# inverter.net
KiCad netlist of a schematic drawn in Altium Designer
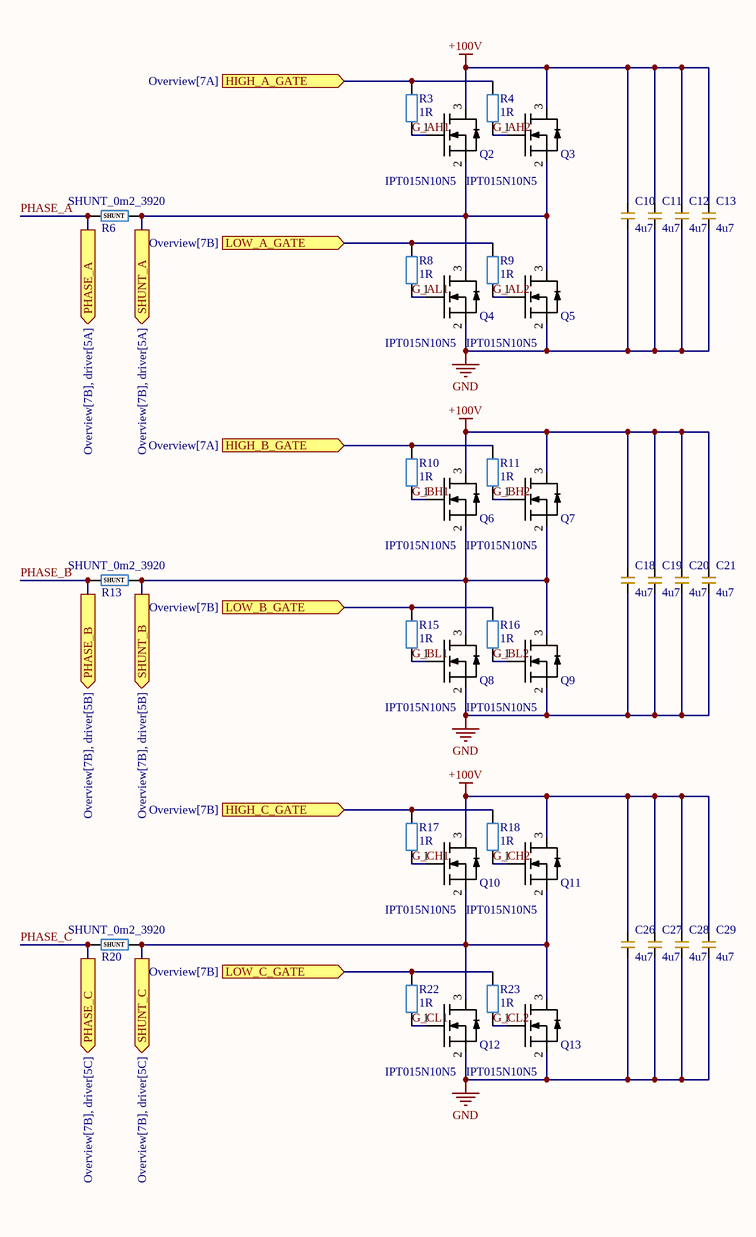
[diagram p0: inverter.SchDoc]

(export (version "E")
  (design (tool "Eeschema 10.0.6"))
  (components
    (comp (ref "C10")
      (value "4u7")
      (footprint "FS32X475K101EGG")
      (description "100V 4.7uF X7R ±10% 1210 Multilayer Ceramic Capacitors MLCC - SMD/SMT ROHS")
      (fields
        (field (name "MFR.") "PSA(Prosperity Dielectrics)")
        (field (name "MFR. PART") "FS32X475K101EGG")
      )
      (libsource (lib "Passive") (part "4u7"))
    )
    (comp (ref "C11")
      (value "4u7")
      (footprint "FS32X475K101EGG")
      (description "100V 4.7uF X7R ±10% 1210 Multilayer Ceramic Capacitors MLCC - SMD/SMT ROHS")
      (fields
        (field (name "MFR.") "PSA(Prosperity Dielectrics)")
        (field (name "MFR. PART") "FS32X475K101EGG")
      )
      (libsource (lib "Passive") (part "4u7"))
    )
    (comp (ref "C12")
      (value "4u7")
      (footprint "FS32X475K101EGG")
      (description "100V 4.7uF X7R ±10% 1210 Multilayer Ceramic Capacitors MLCC - SMD/SMT ROHS")
      (fields
        (field (name "MFR.") "PSA(Prosperity Dielectrics)")
        (field (name "MFR. PART") "FS32X475K101EGG")
      )
      (libsource (lib "Passive") (part "4u7"))
    )
    (comp (ref "C13")
      (value "4u7")
      (footprint "FS32X475K101EGG")
      (description "100V 4.7uF X7R ±10% 1210 Multilayer Ceramic Capacitors MLCC - SMD/SMT ROHS")
      (fields
        (field (name "MFR.") "PSA(Prosperity Dielectrics)")
        (field (name "MFR. PART") "FS32X475K101EGG")
      )
      (libsource (lib "Passive") (part "4u7"))
    )
    (comp (ref "C18")
      (value "4u7")
      (footprint "FS32X475K101EGG")
      (description "100V 4.7uF X7R ±10% 1210 Multilayer Ceramic Capacitors MLCC - SMD/SMT ROHS")
      (fields
        (field (name "MFR.") "PSA(Prosperity Dielectrics)")
        (field (name "MFR. PART") "FS32X475K101EGG")
      )
      (libsource (lib "Passive") (part "4u7"))
    )
    (comp (ref "C19")
      (value "4u7")
      (footprint "FS32X475K101EGG")
      (description "100V 4.7uF X7R ±10% 1210 Multilayer Ceramic Capacitors MLCC - SMD/SMT ROHS")
      (fields
        (field (name "MFR.") "PSA(Prosperity Dielectrics)")
        (field (name "MFR. PART") "FS32X475K101EGG")
      )
      (libsource (lib "Passive") (part "4u7"))
    )
    (comp (ref "C20")
      (value "4u7")
      (footprint "FS32X475K101EGG")
      (description "100V 4.7uF X7R ±10% 1210 Multilayer Ceramic Capacitors MLCC - SMD/SMT ROHS")
      (fields
        (field (name "MFR.") "PSA(Prosperity Dielectrics)")
        (field (name "MFR. PART") "FS32X475K101EGG")
      )
      (libsource (lib "Passive") (part "4u7"))
    )
    (comp (ref "C21")
      (value "4u7")
      (footprint "FS32X475K101EGG")
      (description "100V 4.7uF X7R ±10% 1210 Multilayer Ceramic Capacitors MLCC - SMD/SMT ROHS")
      (fields
        (field (name "MFR.") "PSA(Prosperity Dielectrics)")
        (field (name "MFR. PART") "FS32X475K101EGG")
      )
      (libsource (lib "Passive") (part "4u7"))
    )
    (comp (ref "C26")
      (value "4u7")
      (footprint "FS32X475K101EGG")
      (description "100V 4.7uF X7R ±10% 1210 Multilayer Ceramic Capacitors MLCC - SMD/SMT ROHS")
      (fields
        (field (name "MFR.") "PSA(Prosperity Dielectrics)")
        (field (name "MFR. PART") "FS32X475K101EGG")
      )
      (libsource (lib "Passive") (part "4u7"))
    )
    (comp (ref "C27")
      (value "4u7")
      (footprint "FS32X475K101EGG")
      (description "100V 4.7uF X7R ±10% 1210 Multilayer Ceramic Capacitors MLCC - SMD/SMT ROHS")
      (fields
        (field (name "MFR.") "PSA(Prosperity Dielectrics)")
        (field (name "MFR. PART") "FS32X475K101EGG")
      )
      (libsource (lib "Passive") (part "4u7"))
    )
    (comp (ref "C28")
      (value "4u7")
      (footprint "FS32X475K101EGG")
      (description "100V 4.7uF X7R ±10% 1210 Multilayer Ceramic Capacitors MLCC - SMD/SMT ROHS")
      (fields
        (field (name "MFR.") "PSA(Prosperity Dielectrics)")
        (field (name "MFR. PART") "FS32X475K101EGG")
      )
      (libsource (lib "Passive") (part "4u7"))
    )
    (comp (ref "C29")
      (value "4u7")
      (footprint "FS32X475K101EGG")
      (description "100V 4.7uF X7R ±10% 1210 Multilayer Ceramic Capacitors MLCC - SMD/SMT ROHS")
      (fields
        (field (name "MFR.") "PSA(Prosperity Dielectrics)")
        (field (name "MFR. PART") "FS32X475K101EGG")
      )
      (libsource (lib "Passive") (part "4u7"))
    )
    (comp (ref "Q2")
      (value "IPT015N10N5")
      (footprint "IPT015N10N5")
      (description "100V 500A 533W 1.35mΩ 1 N-channel HSOF-8 MOSFETs ROHS")
      (fields (field (name "MFR.") "Tokmas"))
      (libsource (lib "Active") (part "IPT015N10N5"))
    )
    (comp (ref "Q3")
      (value "IPT015N10N5")
      (footprint "IPT015N10N5")
      (description "100V 500A 533W 1.35mΩ 1 N-channel HSOF-8 MOSFETs ROHS")
      (fields (field (name "MFR.") "Tokmas"))
      (libsource (lib "Active") (part "IPT015N10N5"))
    )
    (comp (ref "Q4")
      (value "IPT015N10N5")
      (footprint "IPT015N10N5")
      (description "100V 500A 533W 1.35mΩ 1 N-channel HSOF-8 MOSFETs ROHS")
      (fields (field (name "MFR.") "Tokmas"))
      (libsource (lib "Active") (part "IPT015N10N5"))
    )
    (comp (ref "Q5")
      (value "IPT015N10N5")
      (footprint "IPT015N10N5")
      (description "100V 500A 533W 1.35mΩ 1 N-channel HSOF-8 MOSFETs ROHS")
      (fields (field (name "MFR.") "Tokmas"))
      (libsource (lib "Active") (part "IPT015N10N5"))
    )
    (comp (ref "Q6")
      (value "IPT015N10N5")
      (footprint "IPT015N10N5")
      (description "100V 500A 533W 1.35mΩ 1 N-channel HSOF-8 MOSFETs ROHS")
      (fields (field (name "MFR.") "Tokmas"))
      (libsource (lib "Active") (part "IPT015N10N5"))
    )
    (comp (ref "Q7")
      (value "IPT015N10N5")
      (footprint "IPT015N10N5")
      (description "100V 500A 533W 1.35mΩ 1 N-channel HSOF-8 MOSFETs ROHS")
      (fields (field (name "MFR.") "Tokmas"))
      (libsource (lib "Active") (part "IPT015N10N5"))
    )
    (comp (ref "Q8")
      (value "IPT015N10N5")
      (footprint "IPT015N10N5")
      (description "100V 500A 533W 1.35mΩ 1 N-channel HSOF-8 MOSFETs ROHS")
      (fields (field (name "MFR.") "Tokmas"))
      (libsource (lib "Active") (part "IPT015N10N5"))
    )
    (comp (ref "Q9")
      (value "IPT015N10N5")
      (footprint "IPT015N10N5")
      (description "100V 500A 533W 1.35mΩ 1 N-channel HSOF-8 MOSFETs ROHS")
      (fields (field (name "MFR.") "Tokmas"))
      (libsource (lib "Active") (part "IPT015N10N5"))
    )
    (comp (ref "Q10")
      (value "IPT015N10N5")
      (footprint "IPT015N10N5")
      (description "100V 500A 533W 1.35mΩ 1 N-channel HSOF-8 MOSFETs ROHS")
      (fields (field (name "MFR.") "Tokmas"))
      (libsource (lib "Active") (part "IPT015N10N5"))
    )
    (comp (ref "Q11")
      (value "IPT015N10N5")
      (footprint "IPT015N10N5")
      (description "100V 500A 533W 1.35mΩ 1 N-channel HSOF-8 MOSFETs ROHS")
      (fields (field (name "MFR.") "Tokmas"))
      (libsource (lib "Active") (part "IPT015N10N5"))
    )
    (comp (ref "Q12")
      (value "IPT015N10N5")
      (footprint "IPT015N10N5")
      (description "100V 500A 533W 1.35mΩ 1 N-channel HSOF-8 MOSFETs ROHS")
      (fields (field (name "MFR.") "Tokmas"))
      (libsource (lib "Active") (part "IPT015N10N5"))
    )
    (comp (ref "Q13")
      (value "IPT015N10N5")
      (footprint "IPT015N10N5")
      (description "100V 500A 533W 1.35mΩ 1 N-channel HSOF-8 MOSFETs ROHS")
      (fields (field (name "MFR.") "Tokmas"))
      (libsource (lib "Active") (part "IPT015N10N5"))
    )
    (comp (ref "R3")
      (value "1R")
      (footprint "RES_0805")
      (description "Resistor SMD 0805 Generic")
      (libsource (lib "Passive") (part "RES_0805"))
    )
    (comp (ref "R4")
      (value "1R")
      (footprint "RES_0805")
      (description "Resistor SMD 0805 Generic")
      (libsource (lib "Passive") (part "RES_0805"))
    )
    (comp (ref "R6")
      (value "SHUNT_0m2_3920")
      (footprint "ASR-M-5-0.2F-t1")
      (description "12W 0.2mΩ Patch Splitter ±200ppm/℃ ±1% 3920 Current Sense Resistors / Shunt Resistors ROHS")
      (fields (field (name "MFR. PART") "ASR-M-5-0.2F-t1") (field (name "MFR.") "Shenzhen Yezhan Elec."))
      (libsource (lib "Passive") (part "SHUNT_0m2_3920"))
    )
    (comp (ref "R8")
      (value "1R")
      (footprint "RES_0805")
      (description "Resistor SMD 0805 Generic")
      (libsource (lib "Passive") (part "RES_0805"))
    )
    (comp (ref "R9")
      (value "1R")
      (footprint "RES_0805")
      (description "Resistor SMD 0805 Generic")
      (libsource (lib "Passive") (part "RES_0805"))
    )
    (comp (ref "R10")
      (value "1R")
      (footprint "RES_0805")
      (description "Resistor SMD 0805 Generic")
      (libsource (lib "Passive") (part "RES_0805"))
    )
    (comp (ref "R11")
      (value "1R")
      (footprint "RES_0805")
      (description "Resistor SMD 0805 Generic")
      (libsource (lib "Passive") (part "RES_0805"))
    )
    (comp (ref "R13")
      (value "SHUNT_0m2_3920")
      (footprint "ASR-M-5-0.2F-t1")
      (description "12W 0.2mΩ Patch Splitter ±200ppm/℃ ±1% 3920 Current Sense Resistors / Shunt Resistors ROHS")
      (fields (field (name "MFR. PART") "ASR-M-5-0.2F-t1") (field (name "MFR.") "Shenzhen Yezhan Elec."))
      (libsource (lib "Passive") (part "SHUNT_0m2_3920"))
    )
    (comp (ref "R15")
      (value "1R")
      (footprint "RES_0805")
      (description "Resistor SMD 0805 Generic")
      (libsource (lib "Passive") (part "RES_0805"))
    )
    (comp (ref "R16")
      (value "1R")
      (footprint "RES_0805")
      (description "Resistor SMD 0805 Generic")
      (libsource (lib "Passive") (part "RES_0805"))
    )
    (comp (ref "R17")
      (value "1R")
      (footprint "RES_0805")
      (description "Resistor SMD 0805 Generic")
      (libsource (lib "Passive") (part "RES_0805"))
    )
    (comp (ref "R18")
      (value "1R")
      (footprint "RES_0805")
      (description "Resistor SMD 0805 Generic")
      (libsource (lib "Passive") (part "RES_0805"))
    )
    (comp (ref "R20")
      (value "SHUNT_0m2_3920")
      (footprint "ASR-M-5-0.2F-t1")
      (description "12W 0.2mΩ Patch Splitter ±200ppm/℃ ±1% 3920 Current Sense Resistors / Shunt Resistors ROHS")
      (fields (field (name "MFR. PART") "ASR-M-5-0.2F-t1") (field (name "MFR.") "Shenzhen Yezhan Elec."))
      (libsource (lib "Passive") (part "SHUNT_0m2_3920"))
    )
    (comp (ref "R22")
      (value "1R")
      (footprint "RES_0805")
      (description "Resistor SMD 0805 Generic")
      (libsource (lib "Passive") (part "RES_0805"))
    )
    (comp (ref "R23")
      (value "1R")
      (footprint "RES_0805")
      (description "Resistor SMD 0805 Generic")
      (libsource (lib "Passive") (part "RES_0805"))
    )
  )
  (nets
    (net (code "1") (name "+100V") (class "Default")
      (node (ref "C10") (pin "2") (pintype "passive"))
      (node (ref "C11") (pin "2") (pintype "passive"))
      (node (ref "C12") (pin "2") (pintype "passive"))
      (node (ref "C13") (pin "2") (pintype "passive"))
      (node (ref "C18") (pin "2") (pintype "passive"))
      (node (ref "C19") (pin "2") (pintype "passive"))
      (node (ref "C20") (pin "2") (pintype "passive"))
      (node (ref "C21") (pin "2") (pintype "passive"))
      (node (ref "C26") (pin "2") (pintype "passive"))
      (node (ref "C27") (pin "2") (pintype "passive"))
      (node (ref "C28") (pin "2") (pintype "passive"))
      (node (ref "C29") (pin "2") (pintype "passive"))
      (node (ref "Q10") (pin "3") (pintype "passive"))
      (node (ref "Q11") (pin "3") (pintype "passive"))
      (node (ref "Q2") (pin "3") (pintype "passive"))
      (node (ref "Q3") (pin "3") (pintype "passive"))
      (node (ref "Q6") (pin "3") (pintype "passive"))
      (node (ref "Q7") (pin "3") (pintype "passive"))
    )
    (net (code "2") (name "/G_AH1") (class "Default")
      (node (ref "Q2") (pin "1") (pinfunction "G_1") (pintype "passive"))
      (node (ref "R3") (pin "1") (pintype "passive"))
    )
    (net (code "3") (name "/G_AH2") (class "Default")
      (node (ref "Q3") (pin "1") (pinfunction "G_1") (pintype "passive"))
      (node (ref "R4") (pin "1") (pintype "passive"))
    )
    (net (code "4") (name "/G_AL1") (class "Default")
      (node (ref "Q4") (pin "1") (pinfunction "G_1") (pintype "passive"))
      (node (ref "R8") (pin "1") (pintype "passive"))
    )
    (net (code "5") (name "/G_AL2") (class "Default")
      (node (ref "Q5") (pin "1") (pinfunction "G_1") (pintype "passive"))
      (node (ref "R9") (pin "1") (pintype "passive"))
    )
    (net (code "6") (name "/G_BH1") (class "Default")
      (node (ref "Q6") (pin "1") (pinfunction "G_1") (pintype "passive"))
      (node (ref "R10") (pin "1") (pintype "passive"))
    )
    (net (code "7") (name "/G_BH2") (class "Default")
      (node (ref "Q7") (pin "1") (pinfunction "G_1") (pintype "passive"))
      (node (ref "R11") (pin "1") (pintype "passive"))
    )
    (net (code "8") (name "/G_BL1") (class "Default")
      (node (ref "Q8") (pin "1") (pinfunction "G_1") (pintype "passive"))
      (node (ref "R15") (pin "1") (pintype "passive"))
    )
    (net (code "9") (name "/G_BL2") (class "Default")
      (node (ref "Q9") (pin "1") (pinfunction "G_1") (pintype "passive"))
      (node (ref "R16") (pin "1") (pintype "passive"))
    )
    (net (code "10") (name "/G_CH1") (class "Default")
      (node (ref "Q10") (pin "1") (pinfunction "G_1") (pintype "passive"))
      (node (ref "R17") (pin "1") (pintype "passive"))
    )
    (net (code "11") (name "/G_CH2") (class "Default")
      (node (ref "Q11") (pin "1") (pinfunction "G_1") (pintype "passive"))
      (node (ref "R18") (pin "1") (pintype "passive"))
    )
    (net (code "12") (name "/G_CL1") (class "Default")
      (node (ref "Q12") (pin "1") (pinfunction "G_1") (pintype "passive"))
      (node (ref "R22") (pin "1") (pintype "passive"))
    )
    (net (code "13") (name "/G_CL2") (class "Default")
      (node (ref "Q13") (pin "1") (pinfunction "G_1") (pintype "passive"))
      (node (ref "R23") (pin "1") (pintype "passive"))
    )
    (net (code "14") (name "/HIGH_A_GATE") (class "Default")
      (node (ref "R3") (pin "2") (pintype "passive"))
      (node (ref "R4") (pin "2") (pintype "passive"))
    )
    (net (code "15") (name "/HIGH_B_GATE") (class "Default")
      (node (ref "R10") (pin "2") (pintype "passive"))
      (node (ref "R11") (pin "2") (pintype "passive"))
    )
    (net (code "16") (name "/HIGH_C_GATE") (class "Default")
      (node (ref "R17") (pin "2") (pintype "passive"))
      (node (ref "R18") (pin "2") (pintype "passive"))
    )
    (net (code "17") (name "/LOW_A_GATE") (class "Default")
      (node (ref "R8") (pin "2") (pintype "passive"))
      (node (ref "R9") (pin "2") (pintype "passive"))
    )
    (net (code "18") (name "/LOW_B_GATE") (class "Default")
      (node (ref "R15") (pin "2") (pintype "passive"))
      (node (ref "R16") (pin "2") (pintype "passive"))
    )
    (net (code "19") (name "/LOW_C_GATE") (class "Default")
      (node (ref "R22") (pin "2") (pintype "passive"))
      (node (ref "R23") (pin "2") (pintype "passive"))
    )
    (net (code "20") (name "/PHASE_A") (class "Default") (node (ref "R6") (pin "1") (pintype "passive")))
    (net (code "21") (name "/PHASE_B") (class "Default") (node (ref "R13") (pin "1") (pintype "passive")))
    (net (code "22") (name "/PHASE_C") (class "Default") (node (ref "R20") (pin "1") (pintype "passive")))
    (net (code "23") (name "/SHUNT_A") (class "Default")
      (node (ref "Q2") (pin "2") (pintype "passive"))
      (node (ref "Q3") (pin "2") (pintype "passive"))
      (node (ref "Q4") (pin "3") (pintype "passive"))
      (node (ref "Q5") (pin "3") (pintype "passive"))
      (node (ref "R6") (pin "2") (pintype "passive"))
    )
    (net (code "24") (name "/SHUNT_B") (class "Default")
      (node (ref "Q6") (pin "2") (pintype "passive"))
      (node (ref "Q7") (pin "2") (pintype "passive"))
      (node (ref "Q8") (pin "3") (pintype "passive"))
      (node (ref "Q9") (pin "3") (pintype "passive"))
      (node (ref "R13") (pin "2") (pintype "passive"))
    )
    (net (code "25") (name "/SHUNT_C") (class "Default")
      (node (ref "Q10") (pin "2") (pintype "passive"))
      (node (ref "Q11") (pin "2") (pintype "passive"))
      (node (ref "Q12") (pin "3") (pintype "passive"))
      (node (ref "Q13") (pin "3") (pintype "passive"))
      (node (ref "R20") (pin "2") (pintype "passive"))
    )
    (net (code "26") (name "GND") (class "Default")
      (node (ref "C10") (pin "1") (pintype "passive"))
      (node (ref "C11") (pin "1") (pintype "passive"))
      (node (ref "C12") (pin "1") (pintype "passive"))
      (node (ref "C13") (pin "1") (pintype "passive"))
      (node (ref "C18") (pin "1") (pintype "passive"))
      (node (ref "C19") (pin "1") (pintype "passive"))
      (node (ref "C20") (pin "1") (pintype "passive"))
      (node (ref "C21") (pin "1") (pintype "passive"))
      (node (ref "C26") (pin "1") (pintype "passive"))
      (node (ref "C27") (pin "1") (pintype "passive"))
      (node (ref "C28") (pin "1") (pintype "passive"))
      (node (ref "C29") (pin "1") (pintype "passive"))
      (node (ref "Q12") (pin "2") (pintype "passive"))
      (node (ref "Q13") (pin "2") (pintype "passive"))
      (node (ref "Q4") (pin "2") (pintype "passive"))
      (node (ref "Q5") (pin "2") (pintype "passive"))
      (node (ref "Q8") (pin "2") (pintype "passive"))
      (node (ref "Q9") (pin "2") (pintype "passive"))
    )
  )
)
